# Warm_White_LEDs.net
KiCad netlist of a schematic drawn in Altium Designer
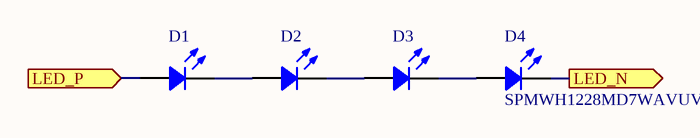
[diagram p0: Warm White LEDs.SchDoc]

(export (version "E")
  (design (tool "Eeschema 10.0.6"))
  (components
    (comp (ref "D1")
      (value "SPMWH1228MD7WAVUVK")
      (footprint "SAMSUNG LM281BPLUS")
      (description "LED")
      (fields (field (name "MANUFACTURER") "Samsung Semiconductor, Inc."))
      (libsource (lib "altiumlibrary.com") (part "LED A-C"))
    )
    (comp (ref "D2")
      (value "SPMWH1228MD7WAVUVK")
      (footprint "SAMSUNG LM281BPLUS")
      (description "LED")
      (fields (field (name "MANUFACTURER") "Samsung Semiconductor, Inc."))
      (libsource (lib "altiumlibrary.com") (part "LED A-C"))
    )
    (comp (ref "D3")
      (value "SPMWH1228MD7WAVUVK")
      (footprint "SAMSUNG LM281BPLUS")
      (description "LED")
      (fields (field (name "MANUFACTURER") "Samsung Semiconductor, Inc."))
      (libsource (lib "altiumlibrary.com") (part "LED A-C"))
    )
    (comp (ref "D4")
      (value "SPMWH1228MD7WAVUVK")
      (footprint "SAMSUNG LM281BPLUS")
      (description "LED")
      (fields (field (name "MANUFACTURER") "Samsung Semiconductor, Inc."))
      (libsource (lib "altiumlibrary.com") (part "LED A-C"))
    )
  )
  (nets
    (net (code "1") (name "/LED_N") (class "Default")
      (node (ref "D4") (pin "C") (pinfunction "C_C") (pintype "passive"))
    )
    (net (code "2") (name "/LED_P") (class "Default")
      (node (ref "D1") (pin "A") (pinfunction "A_A") (pintype "passive"))
    )
    (net (code "3") (name "Net-(D1-PadC)") (class "Default")
      (node (ref "D1") (pin "C") (pinfunction "C_C") (pintype "passive"))
      (node (ref "D2") (pin "A") (pinfunction "A_A") (pintype "passive"))
    )
    (net (code "4") (name "Net-(D2-PadC)") (class "Default")
      (node (ref "D2") (pin "C") (pinfunction "C_C") (pintype "passive"))
      (node (ref "D3") (pin "A") (pinfunction "A_A") (pintype "passive"))
    )
    (net (code "5") (name "Net-(D3-PadC)") (class "Default")
      (node (ref "D3") (pin "C") (pinfunction "C_C") (pintype "passive"))
      (node (ref "D4") (pin "A") (pinfunction "A_A") (pintype "passive"))
    )
  )
)
